# Power_V12P0.net
KiCad netlist of a schematic drawn in Altium Designer
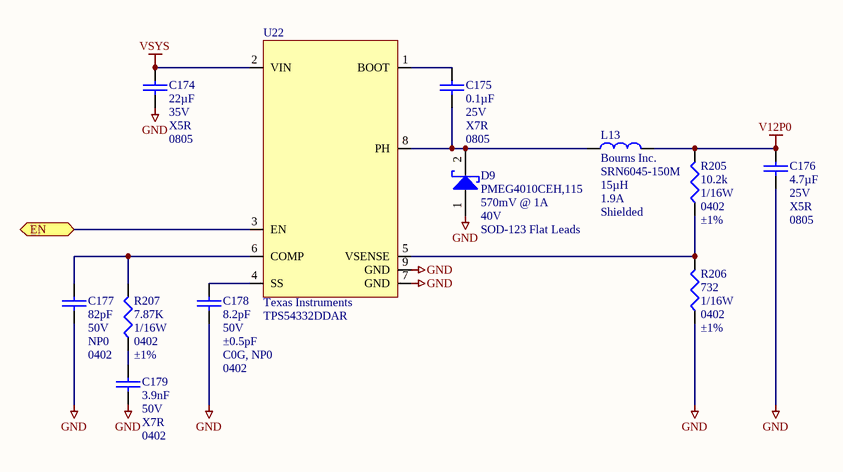
[diagram p0: Power V12P0.SchDoc]

(export (version "E")
  (design (tool "Eeschema 10.0.6"))
  (components
    (comp (ref "C174")
      (value "C_0805_22µF_35V")
      (footprint "C_ERA-0805")
      (description "CAP CER 22UF 35V X5R 0805")
      (fields
        (field (name "MANUFACTURER") "TDK Corporation")
        (field (name "MANUFACTURER PART NUMBER") "C2012X5R1V226M125AC")
        (field (name "CAPACITANCE") "22µF")
        (field (name "VOLTAGE - RATED") "35V")
        (field (name "TEMPERATURE COEFFICIENT") "X5R")
        (field (name "PACKAGE / CASE") "0805")
      )
      (libsource (lib "Cospan Design") (part "C_0805_22µF_35V"))
    )
    (comp (ref "C175")
      (value "0.1uF")
      (footprint "C_ERA-0805")
      (description "CAP CER 1UF 50V X7R 0805")
      (fields
        (field (name "MANUFACTURER") "AVX Corporation")
        (field (name "MANUFACTURER PART NUMBER") "08053C104KAT2A")
        (field (name "CAPACITANCE") "0.1µF")
        (field (name "VOLTAGE - RATED") "25V")
        (field (name "TEMPERATURE COEFFICIENT") "X7R")
        (field (name "PACKAGE / CASE") "0805")
      )
      (libsource (lib "Main Library") (part "C_0805_0.1uF_25V"))
    )
    (comp (ref "C176")
      (value "4.7µF")
      (footprint "C_ERA-0805")
      (description "CAP CER 4.7UF 25V 10% X5R 0805")
      (fields
        (field (name "MANUFACTURER") "Taiyo Yuden")
        (field (name "MANUFACTURER PART NUMBER") "TMK212BJ475KG-T")
        (field (name "CAPACITANCE") "4.7µF")
        (field (name "VOLTAGE - RATED") "25V")
        (field (name "TEMPERATURE COEFFICIENT") "X5R")
        (field (name "PACKAGE / CASE") "0805")
      )
      (libsource (lib "Main Library") (part "C_0805_4.7µF_25V"))
    )
    (comp (ref "C177")
      (value "82pF")
      (footprint "C_ERA-0402")
      (description "CAP CER 82PF 50V 5% C0G 0402")
      (fields
        (field (name "MANUFACTURER") "Murata Electronics North America")
        (field (name "MANUFACTURER PART NUMBER") "GRM1555C1H820FA01D")
        (field (name "CAPACITANCE") "82pF")
        (field (name "VOLTAGE - RATED") "50V")
        (field (name "TEMPERATURE COEFFICIENT") "NP0")
        (field (name "PACKAGE / CASE") "0402")
      )
      (libsource (lib "Main LibraryX") (part "C_0402_82PF_50V"))
    )
    (comp (ref "C178")
      (value "8.2pF")
      (footprint "C_ERA-0402")
      (description "CAP CER 8.2PF 50V NP0 0402")
      (fields
        (field (name "MANUFACTURER") "Yageo")
        (field (name "MANUFACTURER PART NUMBER") "CC0402DRNPO9BN8R2")
        (field (name "CAPACITANCE") "8.2pF")
        (field (name "VOLTAGE - RATED") "50V")
        (field (name "TOLERANCE") "±0.5pF")
        (field (name "TEMPERATURE COEFFICIENT") "C0G, NP0")
        (field (name "PACKAGE / CASE") "0402")
      )
      (libsource (lib "Main LibraryX") (part "C_0402_8.2PF_50V"))
    )
    (comp (ref "C179")
      (value "C_0402_3.9nF")
      (footprint "C_0402")
      (description "CAP CER 3900PF 50V X7R 0402")
      (fields
        (field (name "MANUFACTURER") "Murata Electronics North America")
        (field (name "MANUFACTURER PART NUMBER") "GRM155R71H392KA01D")
        (field (name "CAPACITANCE") "3.9nF")
        (field (name "VOLTAGE - RATED") "50V")
        (field (name "TEMPERATURE COEFFICIENT") "X7R")
        (field (name "PACKAGE / CASE") "0402")
      )
      (libsource (lib "Cospan Design") (part "C_0402_3.9nF"))
    )
    (comp (ref "D9")
      (value "D_SCHOTT_PMEG4010CEH")
      (footprint "D_SOD123F")
      (description "SCHOTTKY RECT 40V 1A SOD123F")
      (fields
        (field (name "MANUFACTURER") "Vishay Semiconductor Diodes Division")
        (field (name "MANUFACTURER PART NUMBER") "PMEG4010CEH,115")
        (field (name "VOLTAGE - FORWARD (VF) (MAX) @ IF") "570mV @ 1A")
        (field (name "VOLTAGE - DC REVERSE (VR) (MAX)") "40V")
        (field (name "PACKAGE / CASE") "SOD-123 Flat Leads")
      )
      (libsource (lib "Main Library") (part "D_SCHOTT_PMEG4010CEH"))
    )
    (comp (ref "L13")
      (value "L_SRN6045-150M")
      (footprint "SRN6045")
      (description "FIXED IND 15UH 1.9A 95.8 MOHM")
      (fields
        (field (name "MANUFACTURER_PART_NUMBER") "SRN6045-150M")
        (field (name "TOLERANCE") "±20%")
        (field (name "MANUFACTURER") "Bourns Inc.")
        (field (name "MANUFACTURER PART NUMBER") "SRN6045-150M")
        (field (name "INDUCTANCE") "15µH")
        (field (name "CURRENT RATING") "1.9A")
        (field (name "SHIELDING") "Shielded")
      )
      (libsource (lib "Cospan Design") (part "L_SRN6045-150M"))
    )
    (comp (ref "R205")
      (value "R_0402_10.2k")
      (footprint "R_0402")
      (description "RES SMD 10.2K OHM 1% 1/16W 0402")
      (fields
        (field (name "MANUFACTURER") "Stackpole Electronics Inc.")
        (field (name "MANUFACTURER PART NUMBER") "RMCF0402FT10K2")
        (field (name "RESISTANCE IN OHMS") "10.2k")
        (field (name "POWER (WATTS)") "1/16W")
        (field (name "CASE") "0402")
        (field (name "TOLERANCE") "±1%")
      )
      (libsource (lib "Cospan Design") (part "R_0402_10.2k"))
    )
    (comp (ref "R206")
      (value "R_0402_732")
      (footprint "R_0402")
      (description "RES SMD 732 OHM 1% 1/16W 0402")
      (fields
        (field (name "MANUFACTURER") "Yageo")
        (field (name "MANUFACTURER PART NUMBER") "RC0402FR-07732RL")
        (field (name "RESISTANCE IN OHMS") "732")
        (field (name "POWER (WATTS)") "1/16W")
        (field (name "CASE") "0402")
        (field (name "TOLERANCE") "±1%")
      )
      (libsource (lib "Cospan Design") (part "R_0402_732"))
    )
    (comp (ref "R207")
      (value "R_0402_7.87K")
      (footprint "R_0402")
      (description "RES 7.87K OHM 1/16W 1% 0402 SMD")
      (fields
        (field (name "MANUFACTURER") "Yageo")
        (field (name "MANUFACTURER PART NUMBER") "RC0402FR-077K87L")
        (field (name "RESISTANCE IN OHMS") "7.87K")
        (field (name "POWER (WATTS)") "1/16W")
        (field (name "CASE") "0402")
        (field (name "TOLERANCE") "±1%")
      )
      (libsource (lib "Main Library") (part "R_0402_7.87K"))
    )
    (comp (ref "U22")
      (value "U_TPS54332DDAR")
      (footprint "DDA0008H")
      (description "IC REG BUCK ADJ 3.5A 8SOPWRPAD")
      (fields
        (field (name "MANUFACTURER") "Texas Instruments")
        (field (name "MANUFACTURER PART NUMBER") "TPS54332DDAR")
      )
      (libsource (lib "Cospan Design") (part "U_TPS54332DDAR"))
    )
  )
  (nets
    (net (code "1") (name "/EN") (class "Default")
      (node (ref "U22") (pin "3") (pinfunction "EN_3") (pintype "passive"))
    )
    (net (code "2") (name "GND") (class "Default")
      (node (ref "C174") (pin "1") (pinfunction "1_1") (pintype "passive"))
      (node (ref "C176") (pin "1") (pinfunction "1_1") (pintype "passive"))
      (node (ref "C177") (pin "1") (pinfunction "1_1") (pintype "passive"))
      (node (ref "C178") (pin "1") (pinfunction "1_1") (pintype "passive"))
      (node (ref "C179") (pin "1") (pinfunction "1_1") (pintype "passive"))
      (node (ref "D9") (pin "1") (pinfunction "A_1") (pintype "passive"))
      (node (ref "R206") (pin "2") (pinfunction "2_2") (pintype "passive"))
      (node (ref "U22") (pin "7") (pinfunction "GND_7") (pintype "passive"))
      (node (ref "U22") (pin "9") (pinfunction "GND_9") (pintype "passive"))
    )
    (net (code "3") (name "Net-(C179-Pad2)") (class "Default")
      (node (ref "C179") (pin "2") (pinfunction "2_2") (pintype "passive"))
      (node (ref "R207") (pin "2") (pinfunction "2_2") (pintype "passive"))
    )
    (net (code "4") (name "Net-(D9-K)") (class "Default")
      (node (ref "C175") (pin "1") (pinfunction "1_1") (pintype "passive"))
      (node (ref "D9") (pin "2") (pinfunction "K_2") (pintype "passive"))
      (node (ref "L13") (pin "2") (pintype "passive"))
      (node (ref "U22") (pin "8") (pinfunction "PH_8") (pintype "passive"))
    )
    (net (code "5") (name "Net-(U22-BOOT)") (class "Default")
      (node (ref "C175") (pin "2") (pinfunction "2_2") (pintype "passive"))
      (node (ref "U22") (pin "1") (pinfunction "BOOT_1") (pintype "passive"))
    )
    (net (code "6") (name "Net-(U22-COMP)") (class "Default")
      (node (ref "C177") (pin "2") (pinfunction "2_2") (pintype "passive"))
      (node (ref "R207") (pin "1") (pinfunction "1_1") (pintype "passive"))
      (node (ref "U22") (pin "6") (pinfunction "COMP_6") (pintype "passive"))
    )
    (net (code "7") (name "Net-(U22-SS)") (class "Default")
      (node (ref "C178") (pin "2") (pinfunction "2_2") (pintype "passive"))
      (node (ref "U22") (pin "4") (pinfunction "SS_4") (pintype "passive"))
    )
    (net (code "8") (name "Net-(U22-VSENSE)") (class "Default")
      (node (ref "R205") (pin "2") (pinfunction "2_2") (pintype "passive"))
      (node (ref "R206") (pin "1") (pinfunction "1_1") (pintype "passive"))
      (node (ref "U22") (pin "5") (pinfunction "VSENSE_5") (pintype "passive"))
    )
    (net (code "9") (name "V12P0") (class "Default")
      (node (ref "C176") (pin "2") (pinfunction "2_2") (pintype "passive"))
      (node (ref "L13") (pin "1") (pintype "passive"))
      (node (ref "R205") (pin "1") (pinfunction "1_1") (pintype "passive"))
    )
    (net (code "10") (name "VSYS") (class "Default")
      (node (ref "C174") (pin "2") (pinfunction "2_2") (pintype "passive"))
      (node (ref "U22") (pin "2") (pinfunction "VIN_2") (pintype "passive"))
    )
  )
)
